# ProPrj_WLED_ESP32_d1_mini_shield_2025-11.net
KiCad netlist of a schematic drawn in EasyEDA Pro
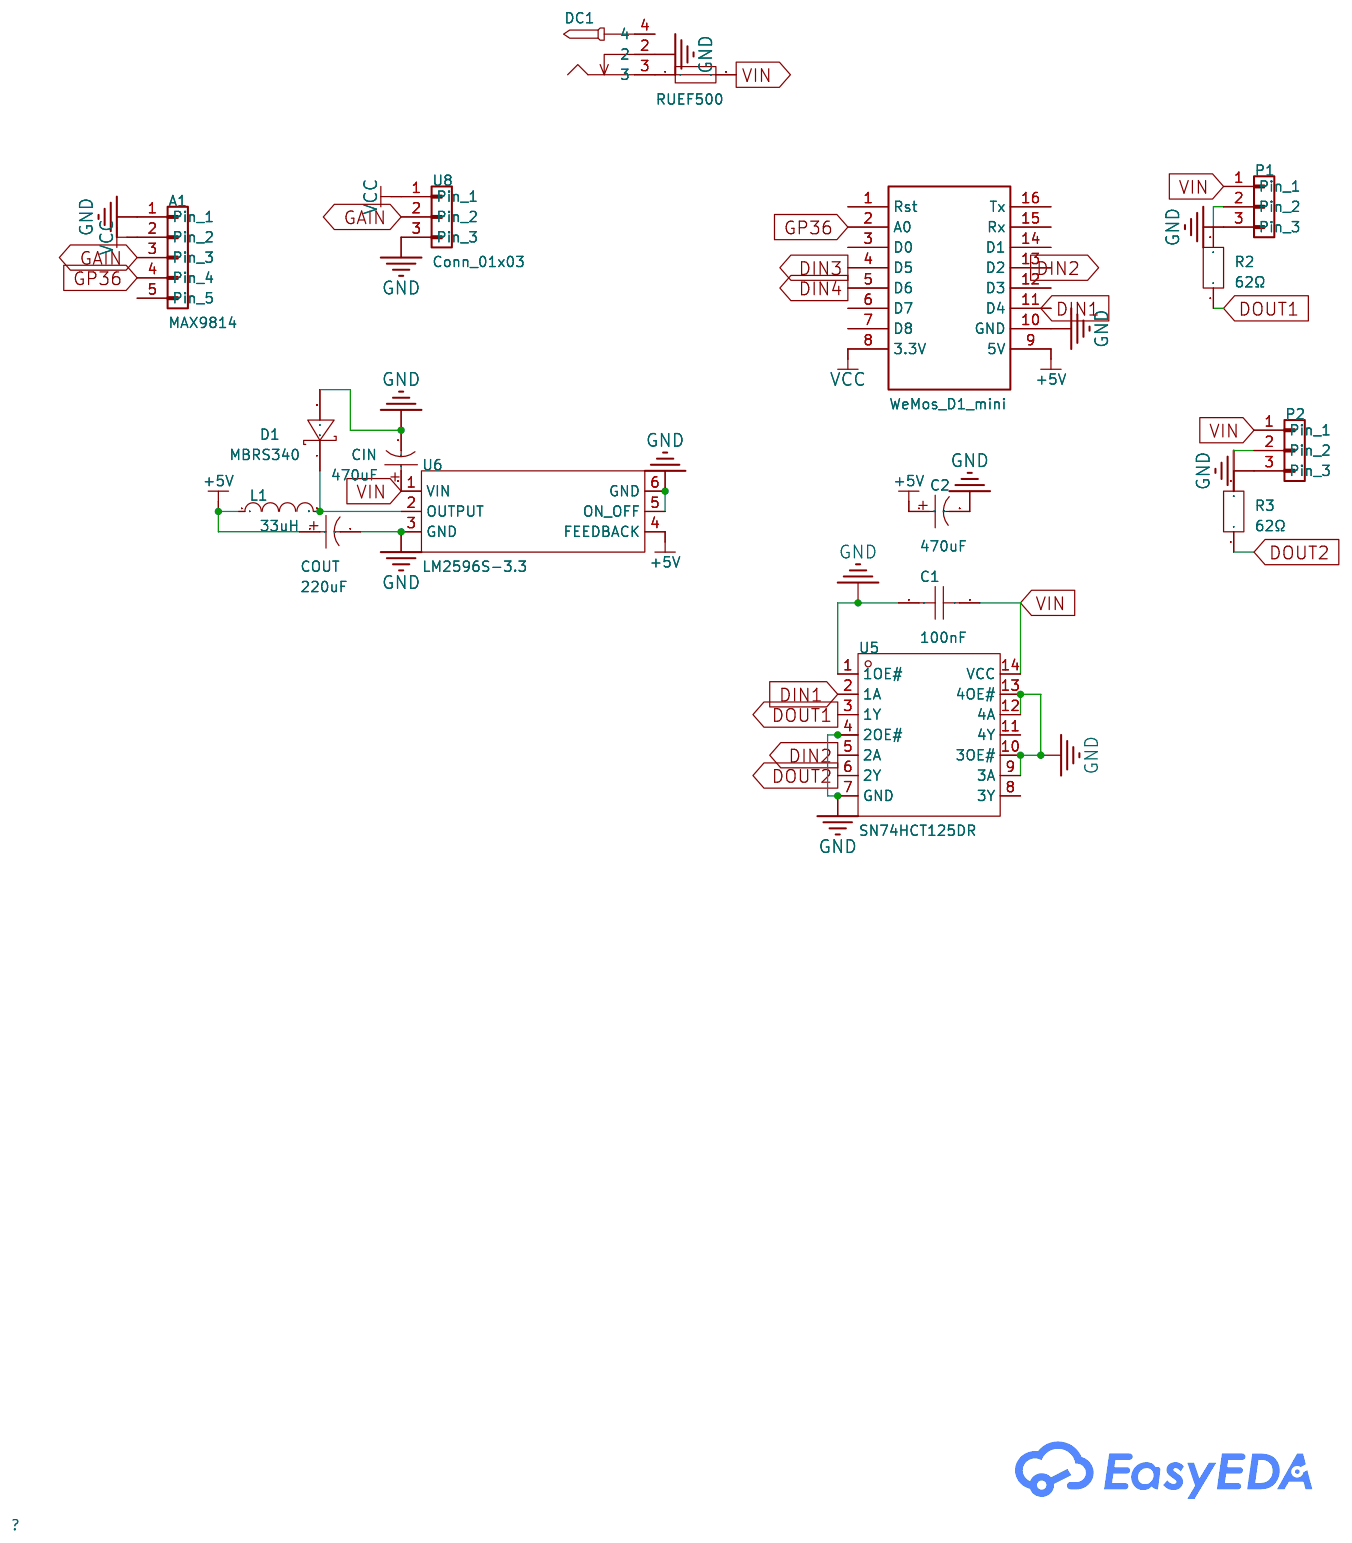
[diagram p0: schematic sheet]

(export (version "E")
  (design (tool "Eeschema 10.0.6"))
  (components
    (comp (ref "A1") (value "MAX9814") (libsource (lib "easyedapro") (part "Conn_01x05")))
    (comp (ref "C1")
      (value "100nF")
      (footprint "easyedapro:CAP-TH_L5.8-W2.8")
      (fields
        (field (name "Manufacturer Part") "CC1H104MC1FD3F6C10SA")
        (field (name "Manufacturer") "Dersonic(德尔创)")
      )
      (libsource (lib "easyedapro") (part "CC1H104MC1FD3F6C10SA"))
    )
    (comp (ref "C2")
      (value "470uF")
      (footprint "easyedapro:CAP-TH_BD8.0-P3.50-D0.6-FD")
      (fields
        (field (name "Manufacturer Part") "KM477M016F12RR0VH2FP0")
        (field (name "Manufacturer") "Chengx(承兴)")
      )
      (libsource (lib "easyedapro") (part "470uf16v"))
    )
    (comp (ref "CIN")
      (value "470uF")
      (footprint "easyedapro:CAP-TH_BD8.0-P3.50-D0.6-FD")
      (fields (field (name "Manufacturer Part") "KM471M025F115A") (field (name "Manufacturer") "CapXon(丰宾)"))
      (libsource (lib "easyedapro") (part "KM471M025F115A"))
    )
    (comp (ref "COUT")
      (value "220uF")
      (footprint "easyedapro:CAP-TH_BD8.0-P3.50-D0.6-FD")
      (fields (field (name "Manufacturer Part") "KM471M025F115A") (field (name "Manufacturer") "CapXon(丰宾)"))
      (libsource (lib "easyedapro") (part "KM471M025F115A"))
    )
    (comp (ref "D1")
      (value "MBRS340")
      (footprint "easyedapro:SMC_L6.9-W5.9-LS7.9-RD")
      (description "Forward Voltage (Vf@If):525mV@3A Reverse Voltage (Vr):40V Rectified Current:3A")
      (fields (field (name "Manufacturer") "onsemi(安森美)"))
      (libsource (lib "easyedapro") (part "MBRS340"))
    )
    (comp (ref "DC1")
      (value "DC-005 2.0")
      (footprint "easyedapro:DC-IN-TH_DC-005-5.5-2.0")
      (fields (field (name "Manufacturer") "BOOMELE(博穆精密)"))
      (libsource (lib "easyedapro") (part "DC-005 5.5-2.0MM"))
    )
    (comp (ref "F1")
      (value "RUEF500")
      (footprint "easyedapro:FUSE-TH_L14.0-W3.0-P10.20-D1.2-S1.2")
      (fields (field (name "Manufacturer") "Littelfuse(美国力特)"))
      (libsource (lib "easyedapro") (part "RUEF500"))
    )
    (comp (ref "L1") (value "10uH") (footprint "easyedapro:L0603") (libsource (lib "easyedapro") (part "电感")))
    (comp (ref "P1") (value "Conn_01x03") (libsource (lib "easyedapro") (part "Conn_01x03")))
    (comp (ref "P2") (value "Conn_01x03") (libsource (lib "easyedapro") (part "Conn_01x03")))
    (comp (ref "R2")
      (value "62Ω")
      (footprint "easyedapro:R1206")
      (fields (field (name "Manufacturer Part") "FRC1206J620 TS") (field (name "Manufacturer") "FOJAN(富捷)"))
      (libsource (lib "easyedapro") (part "FRC1206J620 TS"))
    )
    (comp (ref "R3")
      (value "62Ω")
      (footprint "easyedapro:R1206")
      (fields (field (name "Manufacturer Part") "FRC1206J620 TS") (field (name "Manufacturer") "FOJAN(富捷)"))
      (libsource (lib "easyedapro") (part "FRC1206J620 TS"))
    )
    (comp (ref "U5")
      (value "SN74HCT125DR")
      (footprint "easyedapro:SOIC-14_L8.7-W3.9-P1.27-LS6.0-BL")
      (fields (field (name "Manufacturer") "TI(德州仪器)"))
      (libsource (lib "easyedapro") (part "SN74HCT125DR"))
    )
    (comp (ref "U6")
      (value "LM2596S-3.3")
      (footprint "easyedapro:TO-263-5_L10.1-W8.7-P1.70-LS14.4-BR")
      (fields (field (name "Manufacturer") "Slkor(萨科微)"))
      (libsource (lib "easyedapro") (part "LM2596S-3.3_C19632450"))
    )
    (comp (ref "U7") (value "WeMos_D1_mini") (libsource (lib "easyedapro") (part "WeMos_D1_mini")))
    (comp (ref "U8") (value "Conn_01x03") (libsource (lib "easyedapro") (part "Conn_01x03")))
  )
  (nets
    (net (code "1") (name "+5V") (class "Default")
      (node (ref "C2") (pin "1") (pinfunction "1_1") (pintype "input"))
      (node (ref "COUT") (pin "1") (pinfunction "1_1") (pintype "input"))
      (node (ref "L1") (pin "1") (pinfunction "1_1") (pintype "input"))
      (node (ref "U6") (pin "4") (pinfunction "FEEDBACK_4") (pintype "unspecified"))
      (node (ref "U7") (pin "9") (pinfunction "5V_9") (pintype "unspecified"))
    )
    (net (code "2") (name "DIN1") (class "Default")
      (node (ref "U5") (pin "2") (pinfunction "1A_2") (pintype "unspecified"))
      (node (ref "U7") (pin "11") (pinfunction "D4_11") (pintype "bidirectional"))
    )
    (net (code "3") (name "DIN2") (class "Default")
      (node (ref "U5") (pin "5") (pinfunction "2A_5") (pintype "unspecified"))
      (node (ref "U7") (pin "13") (pinfunction "D2_13") (pintype "bidirectional"))
    )
    (net (code "4") (name "DIN3") (class "Default")
      (node (ref "U7") (pin "4") (pinfunction "D5_4") (pintype "bidirectional"))
    )
    (net (code "5") (name "DIN4") (class "Default")
      (node (ref "U7") (pin "5") (pinfunction "D6_5") (pintype "bidirectional"))
    )
    (net (code "6") (name "DOUT1") (class "Default")
      (node (ref "R2") (pin "1") (pinfunction "1_1") (pintype "unspecified"))
      (node (ref "U5") (pin "3") (pinfunction "1Y_3") (pintype "unspecified"))
    )
    (net (code "7") (name "DOUT2") (class "Default")
      (node (ref "R3") (pin "1") (pinfunction "1_1") (pintype "unspecified"))
      (node (ref "U5") (pin "6") (pinfunction "2Y_6") (pintype "unspecified"))
    )
    (net (code "8") (name "GAIN") (class "Default")
      (node (ref "A1") (pin "3") (pinfunction "Pin_3_3") (pintype "unspecified"))
      (node (ref "U8") (pin "2") (pinfunction "Pin_2_2") (pintype "unspecified"))
    )
    (net (code "9") (name "GND") (class "Default")
      (node (ref "A1") (pin "1") (pinfunction "Pin_1_1") (pintype "unspecified"))
      (node (ref "C1") (pin "1") (pinfunction "1_1") (pintype "unspecified"))
      (node (ref "C2") (pin "2") (pinfunction "2_2") (pintype "input"))
      (node (ref "CIN") (pin "2") (pinfunction "2_2") (pintype "input"))
      (node (ref "COUT") (pin "2") (pinfunction "2_2") (pintype "input"))
      (node (ref "D1") (pin "2") (pinfunction "A_2") (pintype "unspecified"))
      (node (ref "DC1") (pin "2") (pinfunction "2_2") (pintype "unspecified"))
      (node (ref "P1") (pin "3") (pinfunction "Pin_3_3") (pintype "unspecified"))
      (node (ref "P2") (pin "3") (pinfunction "Pin_3_3") (pintype "unspecified"))
      (node (ref "U5") (pin "1") (pinfunction "1OE#_1") (pintype "unspecified"))
      (node (ref "U5") (pin "10") (pinfunction "3OE#_10") (pintype "unspecified"))
      (node (ref "U5") (pin "12") (pinfunction "4A_12") (pintype "unspecified"))
      (node (ref "U5") (pin "13") (pinfunction "4OE#_13") (pintype "unspecified"))
      (node (ref "U5") (pin "4") (pinfunction "2OE#_4") (pintype "unspecified"))
      (node (ref "U5") (pin "7") (pinfunction "GND_7") (pintype "unspecified"))
      (node (ref "U5") (pin "9") (pinfunction "3A_9") (pintype "unspecified"))
      (node (ref "U6") (pin "3") (pinfunction "GND_3") (pintype "unspecified"))
      (node (ref "U6") (pin "5") (pinfunction "ON_OFF_5") (pintype "unspecified"))
      (node (ref "U6") (pin "6") (pinfunction "GND_6") (pintype "unspecified"))
      (node (ref "U7") (pin "10") (pinfunction "GND_10") (pintype "unspecified"))
      (node (ref "U8") (pin "3") (pinfunction "Pin_3_3") (pintype "unspecified"))
    )
    (net (code "10") (name "GP36") (class "Default")
      (node (ref "A1") (pin "4") (pinfunction "Pin_4_4") (pintype "unspecified"))
      (node (ref "U7") (pin "2") (pinfunction "A0_2") (pintype "bidirectional"))
    )
    (net (code "11") (name "Net-(D1-C)") (class "Default")
      (node (ref "D1") (pin "1") (pinfunction "C_1") (pintype "unspecified"))
      (node (ref "L1") (pin "2") (pinfunction "2_2") (pintype "input"))
      (node (ref "U6") (pin "2") (pinfunction "OUTPUT_2") (pintype "unspecified"))
    )
    (net (code "12") (name "Net-(DC1-Pad3)") (class "Default")
      (node (ref "DC1") (pin "3") (pinfunction "3_3") (pintype "unspecified"))
      (node (ref "F1") (pin "1") (pinfunction "1_1") (pintype "unspecified"))
    )
    (net (code "13") (name "Net-(P1-Pin_2)") (class "Default")
      (node (ref "P1") (pin "2") (pinfunction "Pin_2_2") (pintype "unspecified"))
      (node (ref "R2") (pin "2") (pinfunction "2_2") (pintype "unspecified"))
    )
    (net (code "14") (name "Net-(P2-Pin_2)") (class "Default")
      (node (ref "P2") (pin "2") (pinfunction "Pin_2_2") (pintype "unspecified"))
      (node (ref "R3") (pin "2") (pinfunction "2_2") (pintype "unspecified"))
    )
    (net (code "15") (name "VCC") (class "Default")
      (node (ref "A1") (pin "2") (pinfunction "Pin_2_2") (pintype "unspecified"))
      (node (ref "U7") (pin "8") (pinfunction "3.3V_8") (pintype "unspecified"))
      (node (ref "U8") (pin "1") (pinfunction "Pin_1_1") (pintype "unspecified"))
    )
    (net (code "16") (name "VIN") (class "Default")
      (node (ref "C1") (pin "2") (pinfunction "2_2") (pintype "unspecified"))
      (node (ref "CIN") (pin "1") (pinfunction "1_1") (pintype "input"))
      (node (ref "F1") (pin "2") (pinfunction "2_2") (pintype "unspecified"))
      (node (ref "P1") (pin "1") (pinfunction "Pin_1_1") (pintype "unspecified"))
      (node (ref "P2") (pin "1") (pinfunction "Pin_1_1") (pintype "unspecified"))
      (node (ref "U5") (pin "14") (pinfunction "VCC_14") (pintype "unspecified"))
      (node (ref "U6") (pin "1") (pinfunction "VIN_1") (pintype "unspecified"))
    )
    (net (code "17") (name "unconnected-(A1-Pin_5-Pad5)") (class "Default")
      (node (ref "A1") (pin "5") (pinfunction "Pin_5_5") (pintype "unspecified"))
    )
    (net (code "18") (name "unconnected-(DC1-Pad4)") (class "Default")
      (node (ref "DC1") (pin "4") (pinfunction "4_4") (pintype "unspecified"))
    )
    (net (code "19") (name "unconnected-(U5-3Y-Pad8)") (class "Default")
      (node (ref "U5") (pin "8") (pinfunction "3Y_8") (pintype "unspecified"))
    )
    (net (code "20") (name "unconnected-(U5-4Y-Pad11)") (class "Default")
      (node (ref "U5") (pin "11") (pinfunction "4Y_11") (pintype "unspecified"))
    )
    (net (code "21") (name "unconnected-(U7-D0-Pad3)") (class "Default")
      (node (ref "U7") (pin "3") (pinfunction "D0_3") (pintype "bidirectional"))
    )
    (net (code "22") (name "unconnected-(U7-D1-Pad14)") (class "Default")
      (node (ref "U7") (pin "14") (pinfunction "D1_14") (pintype "bidirectional"))
    )
    (net (code "23") (name "unconnected-(U7-D3-Pad12)") (class "Default")
      (node (ref "U7") (pin "12") (pinfunction "D3_12") (pintype "bidirectional"))
    )
    (net (code "24") (name "unconnected-(U7-D7-Pad6)") (class "Default")
      (node (ref "U7") (pin "6") (pinfunction "D7_6") (pintype "bidirectional"))
    )
    (net (code "25") (name "unconnected-(U7-D8-Pad7)") (class "Default")
      (node (ref "U7") (pin "7") (pinfunction "D8_7") (pintype "bidirectional"))
    )
    (net (code "26") (name "unconnected-(U7-Rst-Pad1)") (class "Default")
      (node (ref "U7") (pin "1") (pinfunction "Rst_1") (pintype "bidirectional"))
    )
    (net (code "27") (name "unconnected-(U7-Rx-Pad15)") (class "Default")
      (node (ref "U7") (pin "15") (pinfunction "Rx_15") (pintype "bidirectional"))
    )
    (net (code "28") (name "unconnected-(U7-Tx-Pad16)") (class "Default")
      (node (ref "U7") (pin "16") (pinfunction "Tx_16") (pintype "bidirectional"))
    )
  )
)
